# attinier84-avrisp-shield-mk-1_0.net
KiCad netlist of a schematic drawn in EAGLE
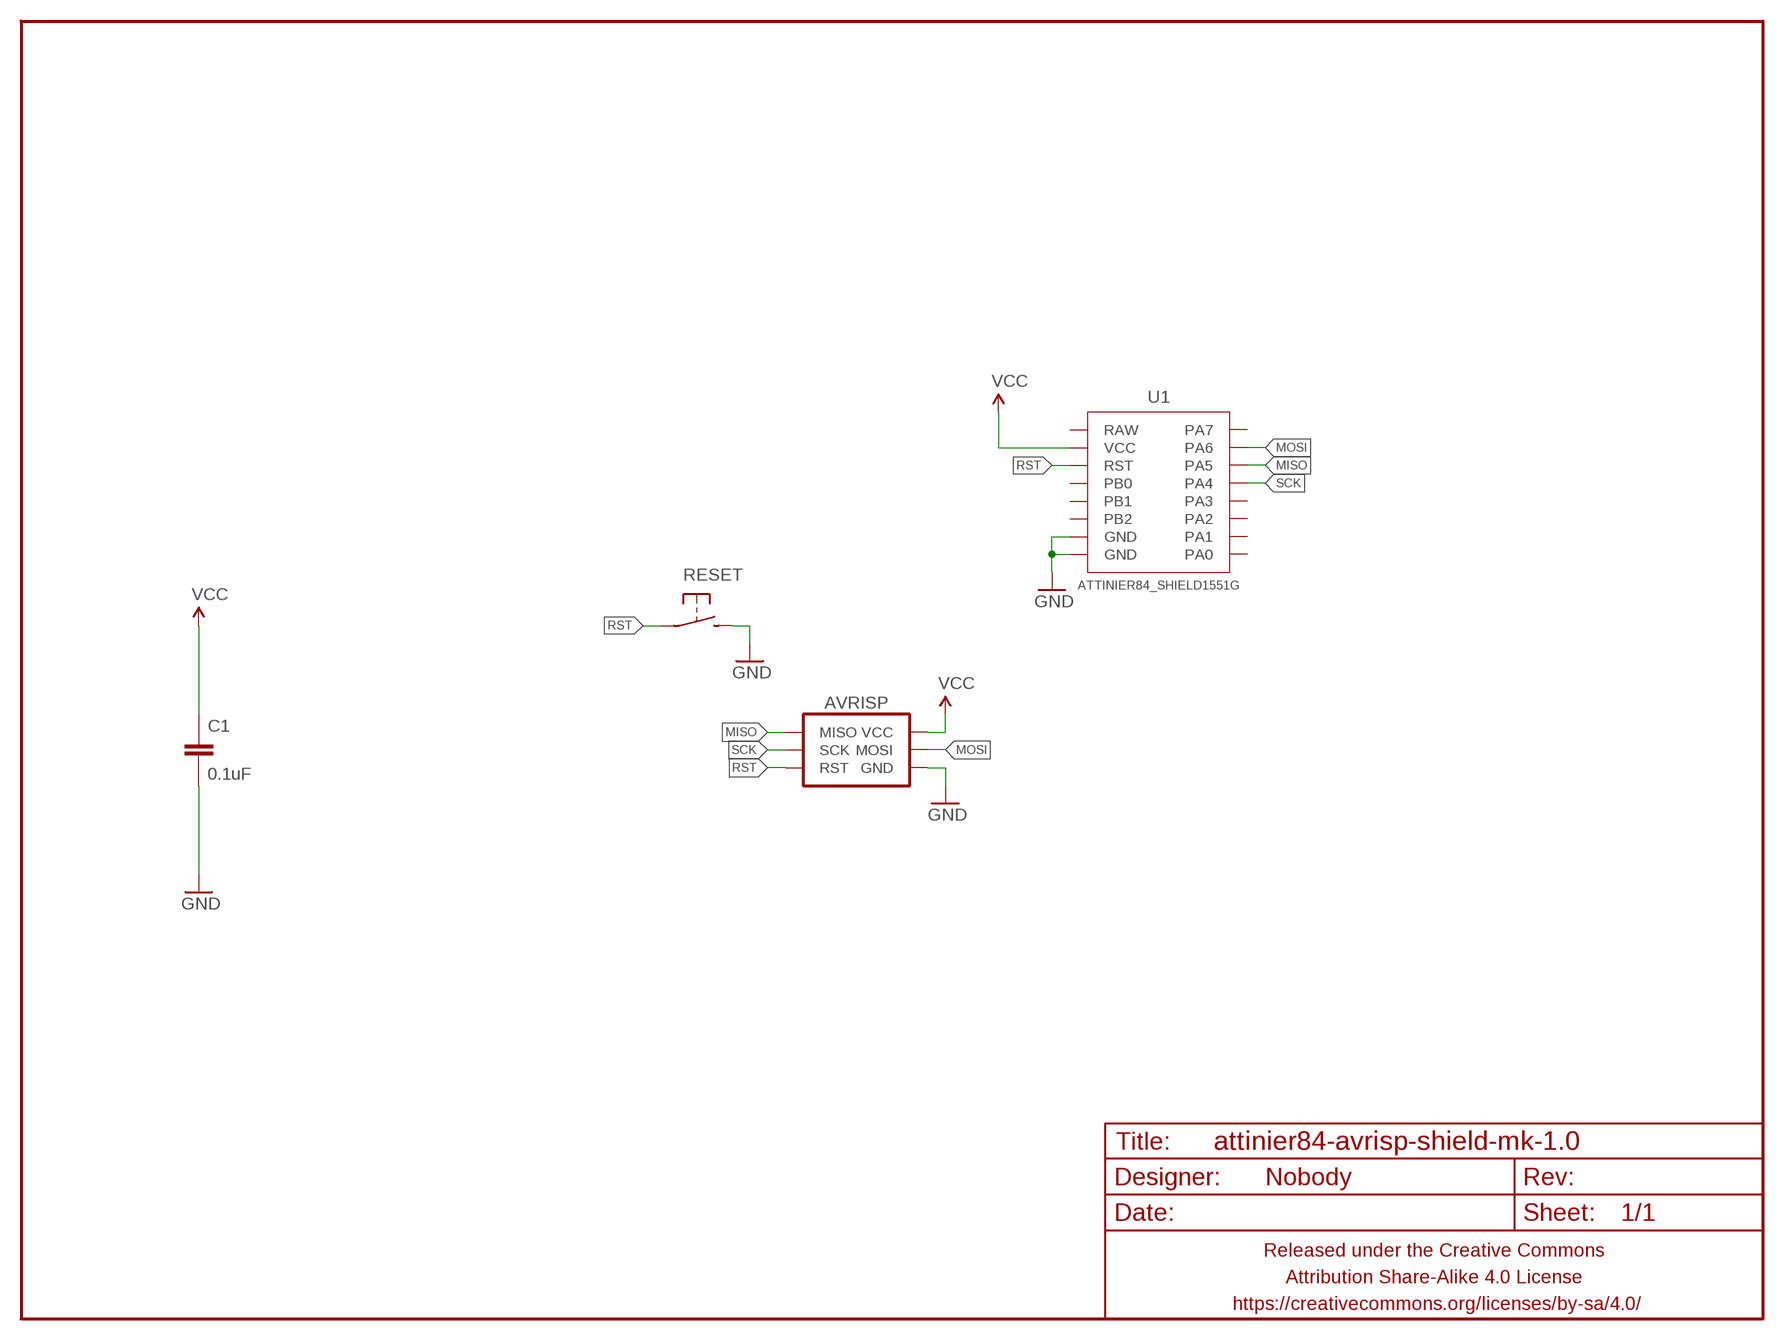
[diagram p0: schematic, sheet 1]

(export (version "E")
  (design (tool "Eeschema 10.0.6"))
  (components
    (comp (ref "AVRISP")
      (value "AVR_SPI_PRG_6PTH-SHROUD")
      (footprint "eagle-import:2X3-SHROUDED")
      (libsource (lib "eagle-import") (part "AVR_SPI_PRG_6PTH-SHROUD"))
    )
    (comp (ref "C1")
      (value "0.1uF")
      (footprint "eagle-import:C025-024X044")
      (libsource (lib "eagle-import") (part "CAPACITOR-CERAMIC025-024X044"))
    )
    (comp (ref "FRAME1")
      (value "FRAME-LETTERNO_PACKAGE")
      (footprint "eagle-import:DUMMY")
      (fields (field (name "DESIGNER") "Nobody"))
      (libsource (lib "eagle-import") (part "FRAME-LETTERNO_PACKAGE"))
    )
    (comp (ref "RESET")
      (value "SPST-NO-TACT6MM-PTH-SMALL-PADS")
      (footprint "eagle-import:DTS-6-SMALL-PADS")
      (libsource (lib "eagle-import") (part "SPST-NO-TACT6MM-PTH-SMALL-PADS"))
    )
    (comp (ref "U1")
      (value "ATTINIER84_SHIELD1551G")
      (footprint "eagle-import:ATTINIER84_SHIELD2")
      (libsource (lib "eagle-import") (part "ATTINIER84_SHIELD1551G"))
    )
  )
  (nets
    (net (code "1") (name "GND") (class "Default")
      (node (ref "AVRISP") (pin "6") (pinfunction "GND_6") (pintype "passive"))
      (node (ref "C1") (pin "2") (pinfunction "2_2") (pintype "passive"))
      (node (ref "RESET") (pin "3") (pinfunction "2_3") (pintype "passive"))
      (node (ref "RESET") (pin "4") (pinfunction "2_4") (pintype "passive"))
      (node (ref "U1") (pin "GND@1") (pinfunction "GND_GND@1") (pintype "bidirectional"))
      (node (ref "U1") (pin "GND@2") (pinfunction "GND_GND@2") (pintype "bidirectional"))
    )
    (net (code "2") (name "MISO") (class "Default")
      (node (ref "AVRISP") (pin "1") (pinfunction "MISO_1") (pintype "passive"))
      (node (ref "U1") (pin "PA5") (pinfunction "PA5_PA5") (pintype "bidirectional"))
    )
    (net (code "3") (name "MOSI") (class "Default")
      (node (ref "AVRISP") (pin "4") (pinfunction "MOSI_4") (pintype "passive"))
      (node (ref "U1") (pin "PA6") (pinfunction "PA6_PA6") (pintype "bidirectional"))
    )
    (net (code "4") (name "RST") (class "Default")
      (node (ref "AVRISP") (pin "5") (pinfunction "RST_5") (pintype "passive"))
      (node (ref "RESET") (pin "1") (pinfunction "1_1") (pintype "passive"))
      (node (ref "RESET") (pin "2") (pinfunction "1_2") (pintype "passive"))
      (node (ref "U1") (pin "RST") (pinfunction "RST_RST") (pintype "bidirectional"))
    )
    (net (code "5") (name "SCK") (class "Default")
      (node (ref "AVRISP") (pin "3") (pinfunction "SCK_3") (pintype "passive"))
      (node (ref "U1") (pin "PA4") (pinfunction "PA4_PA4") (pintype "bidirectional"))
    )
    (net (code "6") (name "VCC") (class "Default")
      (node (ref "AVRISP") (pin "2") (pinfunction "VCC_2") (pintype "passive"))
      (node (ref "C1") (pin "1") (pinfunction "1_1") (pintype "passive"))
      (node (ref "U1") (pin "VCC") (pinfunction "VCC_VCC") (pintype "bidirectional"))
    )
    (net (code "7") (name "unconnected-(U1-PadPA0)") (class "Default")
      (node (ref "U1") (pin "PA0") (pinfunction "PA0_PA0") (pintype "bidirectional"))
    )
    (net (code "8") (name "unconnected-(U1-PadPA1)") (class "Default")
      (node (ref "U1") (pin "PA1") (pinfunction "PA1_PA1") (pintype "bidirectional"))
    )
    (net (code "9") (name "unconnected-(U1-PadPA2)") (class "Default")
      (node (ref "U1") (pin "PA2") (pinfunction "PA2_PA2") (pintype "bidirectional"))
    )
    (net (code "10") (name "unconnected-(U1-PadPA3)") (class "Default")
      (node (ref "U1") (pin "PA3") (pinfunction "PA3_PA3") (pintype "bidirectional"))
    )
    (net (code "11") (name "unconnected-(U1-PadPA7)") (class "Default")
      (node (ref "U1") (pin "PA7") (pinfunction "PA7_PA7") (pintype "bidirectional"))
    )
    (net (code "12") (name "unconnected-(U1-PadPB0)") (class "Default")
      (node (ref "U1") (pin "PB0") (pinfunction "PB0_PB0") (pintype "bidirectional"))
    )
    (net (code "13") (name "unconnected-(U1-PadPB1)") (class "Default")
      (node (ref "U1") (pin "PB1") (pinfunction "PB1_PB1") (pintype "bidirectional"))
    )
    (net (code "14") (name "unconnected-(U1-PadPB2)") (class "Default")
      (node (ref "U1") (pin "PB2") (pinfunction "PB2_PB2") (pintype "bidirectional"))
    )
    (net (code "15") (name "unconnected-(U1-PadRAW)") (class "Default")
      (node (ref "U1") (pin "RAW") (pinfunction "RAW_RAW") (pintype "bidirectional"))
    )
  )
)
